# ignition4.net
KiCad netlist of a schematic drawn in EAGLE
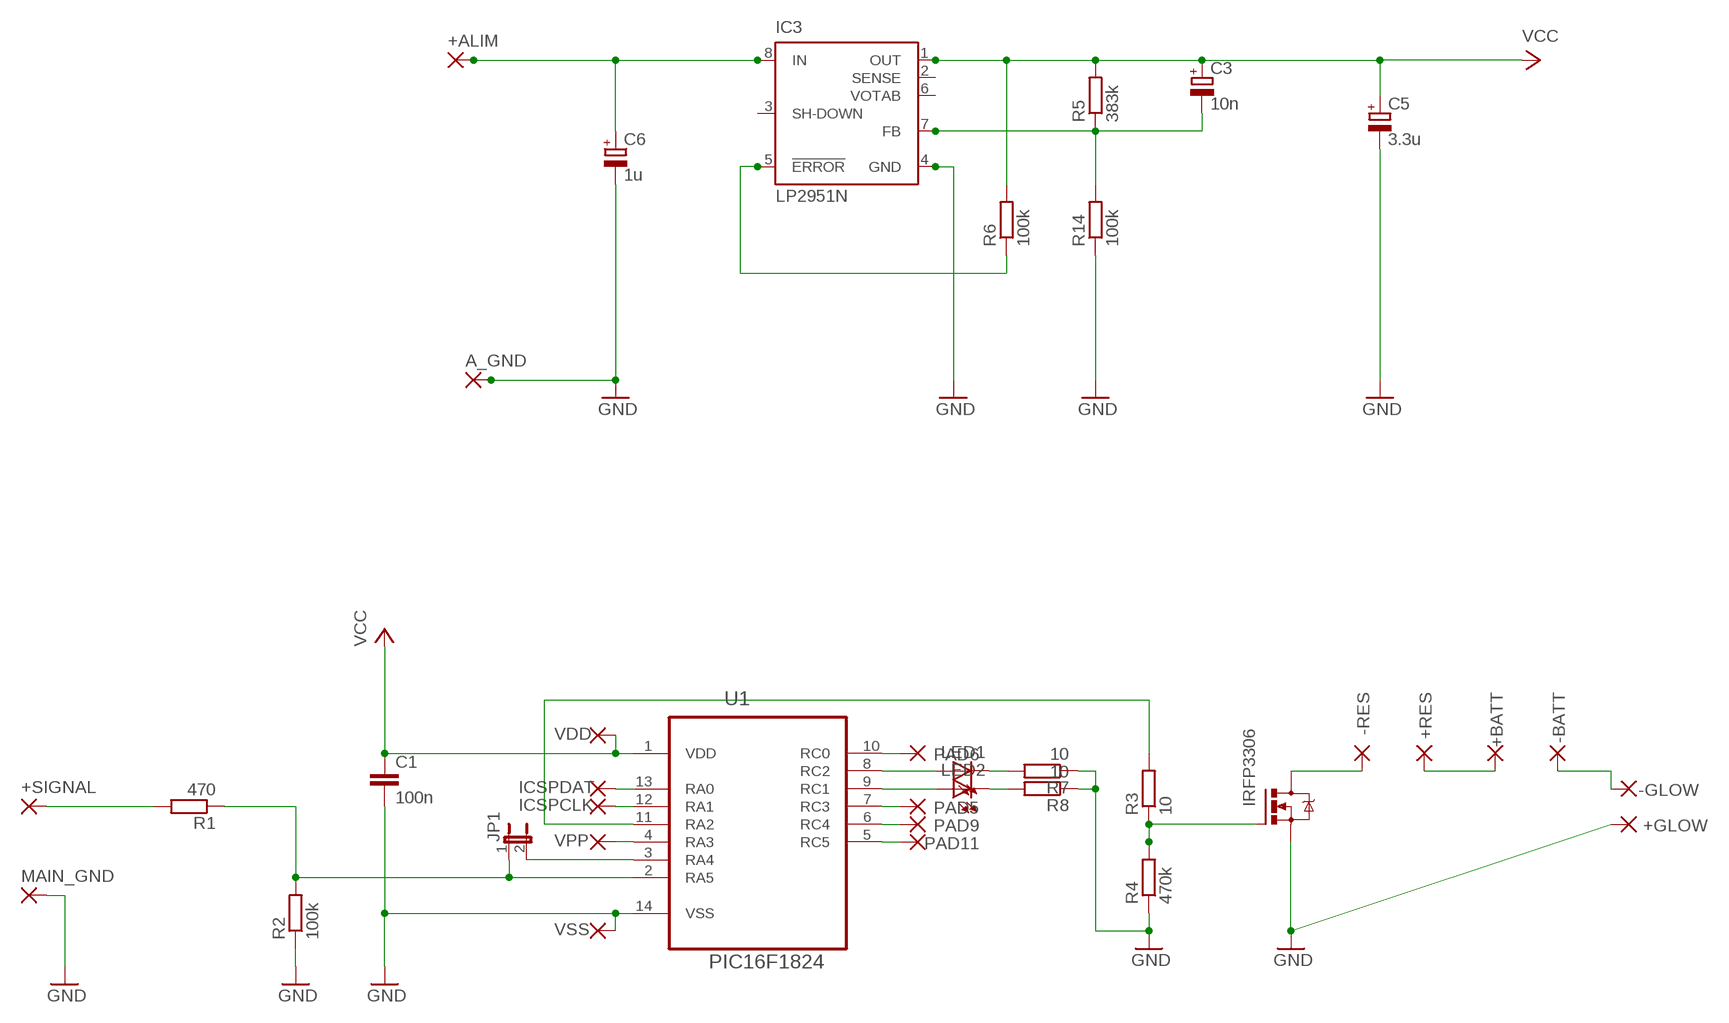
[diagram p0: schematic, sheet 1]

(export (version "E")
  (design (tool "Eeschema 10.0.6"))
  (components
    (comp (ref "+ALIM")
      (value "2,15/1,0")
      (footprint "eagle-import:2,15_1,0")
      (libsource (lib "eagle-import") (part "2,15/1,0"))
    )
    (comp (ref "+BATT")
      (value "WIREPAD3,17/1,3")
      (footprint "eagle-import:3,17_1,3")
      (libsource (lib "eagle-import") (part "WIREPAD3,17/1,3"))
    )
    (comp (ref "+GLOW")
      (value "WIREPAD3,17/1,3")
      (footprint "eagle-import:3,17_1,3")
      (libsource (lib "eagle-import") (part "WIREPAD3,17/1,3"))
    )
    (comp (ref "+RES")
      (value "WIREPAD3,17/1,3")
      (footprint "eagle-import:3,17_1,3")
      (libsource (lib "eagle-import") (part "WIREPAD3,17/1,3"))
    )
    (comp (ref "+SIGNAL")
      (value "2,15/1,0")
      (footprint "eagle-import:2,15_1,0")
      (libsource (lib "eagle-import") (part "2,15/1,0"))
    )
    (comp (ref "-BATT")
      (value "WIREPAD3,17/1,3")
      (footprint "eagle-import:3,17_1,3")
      (libsource (lib "eagle-import") (part "WIREPAD3,17/1,3"))
    )
    (comp (ref "-GLOW")
      (value "WIREPAD3,17/1,3")
      (footprint "eagle-import:3,17_1,3")
      (libsource (lib "eagle-import") (part "WIREPAD3,17/1,3"))
    )
    (comp (ref "-RES")
      (value "WIREPAD3,17/1,3")
      (footprint "eagle-import:3,17_1,3")
      (libsource (lib "eagle-import") (part "WIREPAD3,17/1,3"))
    )
    (comp (ref "A_GND")
      (value "2,15/1,0")
      (footprint "eagle-import:2,15_1,0")
      (libsource (lib "eagle-import") (part "2,15/1,0"))
    )
    (comp (ref "C1")
      (value "100n")
      (footprint "eagle-import:C050-035X075")
      (libsource (lib "eagle-import") (part "C-EU050-035X075"))
    )
    (comp (ref "C3")
      (value "10n")
      (footprint "eagle-import:E5-6")
      (libsource (lib "eagle-import") (part "CPOL-EUE5-6"))
    )
    (comp (ref "C5")
      (value "3.3u")
      (footprint "eagle-import:E2,5-5")
      (libsource (lib "eagle-import") (part "CPOL-EUE2.5-5"))
    )
    (comp (ref "C6")
      (value "1u")
      (footprint "eagle-import:E2,5-5")
      (libsource (lib "eagle-import") (part "CPOL-EUE2.5-5"))
    )
    (comp (ref "IC3")
      (value "LP2951N")
      (footprint "eagle-import:DIL08")
      (libsource (lib "eagle-import") (part "LP2951N"))
    )
    (comp (ref "ICSPCLK")
      (value "2,15/1,0")
      (footprint "eagle-import:2,15_1,0")
      (libsource (lib "eagle-import") (part "2,15/1,0"))
    )
    (comp (ref "ICSPDAT")
      (value "2,15/1,0")
      (footprint "eagle-import:2,15_1,0")
      (libsource (lib "eagle-import") (part "2,15/1,0"))
    )
    (comp (ref "JP1")
      (value "JP1E")
      (footprint "eagle-import:JP1")
      (libsource (lib "eagle-import") (part "JP1E"))
    )
    (comp (ref "LED1")
      (value "LED3MM")
      (footprint "eagle-import:LED3MM")
      (libsource (lib "eagle-import") (part "LED3MM"))
    )
    (comp (ref "LED2")
      (value "LED3MM")
      (footprint "eagle-import:LED3MM")
      (libsource (lib "eagle-import") (part "LED3MM"))
    )
    (comp (ref "MAIN_GND")
      (value "2,15/1,0")
      (footprint "eagle-import:2,15_1,0")
      (libsource (lib "eagle-import") (part "2,15/1,0"))
    )
    (comp (ref "PAD5")
      (value "2,15/1,0")
      (footprint "eagle-import:2,15_1,0")
      (libsource (lib "eagle-import") (part "2,15/1,0"))
    )
    (comp (ref "PAD6")
      (value "2,15/1,0")
      (footprint "eagle-import:2,15_1,0")
      (libsource (lib "eagle-import") (part "2,15/1,0"))
    )
    (comp (ref "PAD9")
      (value "2,15/1,0")
      (footprint "eagle-import:2,15_1,0")
      (libsource (lib "eagle-import") (part "2,15/1,0"))
    )
    (comp (ref "PAD11")
      (value "2,15/1,0")
      (footprint "eagle-import:2,15_1,0")
      (libsource (lib "eagle-import") (part "2,15/1,0"))
    )
    (comp (ref "Q2")
      (value "IRFP3306")
      (footprint "eagle-import:TO247BV")
      (libsource (lib "eagle-import") (part "IRFPC40"))
    )
    (comp (ref "R1")
      (value "470")
      (footprint "eagle-import:0207_7")
      (libsource (lib "eagle-import") (part "R-EU_0207/7"))
    )
    (comp (ref "R2")
      (value "100k")
      (footprint "eagle-import:0207_7")
      (libsource (lib "eagle-import") (part "R-EU_0207/7"))
    )
    (comp (ref "R3")
      (value "10")
      (footprint "eagle-import:0207_7")
      (libsource (lib "eagle-import") (part "R-EU_0207/7"))
    )
    (comp (ref "R4")
      (value "470k")
      (footprint "eagle-import:0207_7")
      (libsource (lib "eagle-import") (part "R-EU_0207/7"))
    )
    (comp (ref "R5")
      (value "383k")
      (footprint "eagle-import:0207_7")
      (libsource (lib "eagle-import") (part "R-EU_0207/7"))
    )
    (comp (ref "R6")
      (value "100k")
      (footprint "eagle-import:0207_7")
      (libsource (lib "eagle-import") (part "R-EU_0207/7"))
    )
    (comp (ref "R7")
      (value "10")
      (footprint "eagle-import:0207_7")
      (libsource (lib "eagle-import") (part "R-EU_0207/7"))
    )
    (comp (ref "R8")
      (value "10")
      (footprint "eagle-import:0207_7")
      (libsource (lib "eagle-import") (part "R-EU_0207/7"))
    )
    (comp (ref "R14")
      (value "100k")
      (footprint "eagle-import:0207_7")
      (libsource (lib "eagle-import") (part "R-EU_0207/7"))
    )
    (comp (ref "U1")
      (value "PIC16F1824")
      (footprint "eagle-import:DIP254P762X533-14")
      (fields (field (name "MPN") "PIC16F1824-I/P"))
      (libsource (lib "eagle-import") (part "PIC16F1824-I/P"))
    )
    (comp (ref "VDD")
      (value "WIREPAD2,15/1,0")
      (footprint "eagle-import:2,15_1,0")
      (libsource (lib "eagle-import") (part "WIREPAD2,15/1,0"))
    )
    (comp (ref "VPP")
      (value "2,15/1,0")
      (footprint "eagle-import:2,15_1,0")
      (libsource (lib "eagle-import") (part "2,15/1,0"))
    )
    (comp (ref "VSS")
      (value "WIREPAD2,15/1,0")
      (footprint "eagle-import:2,15_1,0")
      (libsource (lib "eagle-import") (part "WIREPAD2,15/1,0"))
    )
  )
  (nets
    (net (code "1") (name "GND") (class "Default")
      (node (ref "+GLOW") (pin "1") (pinfunction "P_1") (pintype "passive"))
      (node (ref "A_GND") (pin "1") (pinfunction "P_1") (pintype "passive"))
      (node (ref "C1") (pin "2") (pinfunction "2_2") (pintype "passive"))
      (node (ref "C5") (pin "-") (pinfunction "-_-") (pintype "passive"))
      (node (ref "C6") (pin "-") (pinfunction "-_-") (pintype "passive"))
      (node (ref "IC3") (pin "4") (pinfunction "GND_4") (pintype "power_in"))
      (node (ref "MAIN_GND") (pin "1") (pinfunction "P_1") (pintype "passive"))
      (node (ref "Q2") (pin "S") (pinfunction "S_S") (pintype "passive"))
      (node (ref "R14") (pin "1") (pinfunction "1_1") (pintype "passive"))
      (node (ref "R2") (pin "1") (pinfunction "1_1") (pintype "passive"))
      (node (ref "R4") (pin "1") (pinfunction "1_1") (pintype "passive"))
      (node (ref "R7") (pin "1") (pinfunction "1_1") (pintype "passive"))
      (node (ref "R8") (pin "1") (pinfunction "1_1") (pintype "passive"))
      (node (ref "U1") (pin "14") (pinfunction "VSS_14") (pintype "power_in"))
      (node (ref "VSS") (pin "1") (pinfunction "P_1") (pintype "passive"))
    )
    (net (code "2") (name "Net-(+ALIM-P)") (class "Default")
      (node (ref "+ALIM") (pin "1") (pinfunction "P_1") (pintype "passive"))
      (node (ref "C6") (pin "+") (pinfunction "+_+") (pintype "passive"))
      (node (ref "IC3") (pin "8") (pinfunction "IN_8") (pintype "input"))
    )
    (net (code "3") (name "Net-(+BATT-P)") (class "Default")
      (node (ref "+BATT") (pin "1") (pinfunction "P_1") (pintype "passive"))
      (node (ref "+RES") (pin "1") (pinfunction "P_1") (pintype "passive"))
    )
    (net (code "4") (name "Net-(+SIGNAL-P)") (class "Default")
      (node (ref "+SIGNAL") (pin "1") (pinfunction "P_1") (pintype "passive"))
      (node (ref "R1") (pin "2") (pinfunction "2_2") (pintype "passive"))
    )
    (net (code "5") (name "Net-(-BATT-P)") (class "Default")
      (node (ref "-BATT") (pin "1") (pinfunction "P_1") (pintype "passive"))
      (node (ref "-GLOW") (pin "1") (pinfunction "P_1") (pintype "passive"))
    )
    (net (code "6") (name "Net-(-RES-P)") (class "Default")
      (node (ref "-RES") (pin "1") (pinfunction "P_1") (pintype "passive"))
      (node (ref "Q2") (pin "D") (pinfunction "D_D") (pintype "passive"))
    )
    (net (code "7") (name "Net-(IC3-FB)") (class "Default")
      (node (ref "C3") (pin "-") (pinfunction "-_-") (pintype "passive"))
      (node (ref "IC3") (pin "7") (pinfunction "FB_7") (pintype "input"))
      (node (ref "R14") (pin "2") (pinfunction "2_2") (pintype "passive"))
      (node (ref "R5") (pin "1") (pinfunction "1_1") (pintype "passive"))
    )
    (net (code "8") (name "Net-(IC3-~{ERROR})") (class "Default")
      (node (ref "IC3") (pin "5") (pinfunction "~{ERROR}_5") (pintype "output"))
      (node (ref "R6") (pin "1") (pinfunction "1_1") (pintype "passive"))
    )
    (net (code "9") (name "Net-(ICSPCLK-P)") (class "Default")
      (node (ref "ICSPCLK") (pin "1") (pinfunction "P_1") (pintype "passive"))
      (node (ref "U1") (pin "12") (pinfunction "RA1_12") (pintype "bidirectional"))
    )
    (net (code "10") (name "Net-(ICSPDAT-P)") (class "Default")
      (node (ref "ICSPDAT") (pin "1") (pinfunction "P_1") (pintype "passive"))
      (node (ref "U1") (pin "13") (pinfunction "RA0_13") (pintype "bidirectional"))
    )
    (net (code "11") (name "Net-(LED1-C)") (class "Default")
      (node (ref "LED1") (pin "K") (pinfunction "C_K") (pintype "passive"))
      (node (ref "R7") (pin "2") (pinfunction "2_2") (pintype "passive"))
    )
    (net (code "12") (name "Net-(LED2-C)") (class "Default")
      (node (ref "LED2") (pin "K") (pinfunction "C_K") (pintype "passive"))
      (node (ref "R8") (pin "2") (pinfunction "2_2") (pintype "passive"))
    )
    (net (code "13") (name "Net-(PAD5-P)") (class "Default")
      (node (ref "PAD5") (pin "1") (pinfunction "P_1") (pintype "passive"))
      (node (ref "U1") (pin "7") (pinfunction "RC3_7") (pintype "bidirectional"))
    )
    (net (code "14") (name "Net-(PAD6-P)") (class "Default")
      (node (ref "PAD6") (pin "1") (pinfunction "P_1") (pintype "passive"))
      (node (ref "U1") (pin "10") (pinfunction "RC0_10") (pintype "bidirectional"))
    )
    (net (code "15") (name "Net-(PAD9-P)") (class "Default")
      (node (ref "PAD9") (pin "1") (pinfunction "P_1") (pintype "passive"))
      (node (ref "U1") (pin "6") (pinfunction "RC4_6") (pintype "bidirectional"))
    )
    (net (code "16") (name "Net-(PAD11-P)") (class "Default")
      (node (ref "PAD11") (pin "1") (pinfunction "P_1") (pintype "passive"))
      (node (ref "U1") (pin "5") (pinfunction "RC5_5") (pintype "bidirectional"))
    )
    (net (code "17") (name "Net-(Q2-PadG)") (class "Default")
      (node (ref "Q2") (pin "G") (pinfunction "G_G") (pintype "passive"))
      (node (ref "R3") (pin "1") (pinfunction "1_1") (pintype "passive"))
      (node (ref "R4") (pin "2") (pinfunction "2_2") (pintype "passive"))
    )
    (net (code "18") (name "Net-(U1-RA2)") (class "Default")
      (node (ref "R3") (pin "2") (pinfunction "2_2") (pintype "passive"))
      (node (ref "U1") (pin "11") (pinfunction "RA2_11") (pintype "bidirectional"))
    )
    (net (code "19") (name "Net-(U1-RA3)") (class "Default")
      (node (ref "U1") (pin "4") (pinfunction "RA3_4") (pintype "input"))
      (node (ref "VPP") (pin "1") (pinfunction "P_1") (pintype "passive"))
    )
    (net (code "20") (name "Net-(U1-RA4)") (class "Default")
      (node (ref "JP1") (pin "2") (pinfunction "2_2") (pintype "passive"))
      (node (ref "U1") (pin "3") (pinfunction "RA4_3") (pintype "bidirectional"))
    )
    (net (code "21") (name "Net-(U1-RA5)") (class "Default")
      (node (ref "JP1") (pin "1") (pinfunction "1_1") (pintype "passive"))
      (node (ref "R1") (pin "1") (pinfunction "1_1") (pintype "passive"))
      (node (ref "R2") (pin "2") (pinfunction "2_2") (pintype "passive"))
      (node (ref "U1") (pin "2") (pinfunction "RA5_2") (pintype "bidirectional"))
    )
    (net (code "22") (name "Net-(U1-RC1)") (class "Default")
      (node (ref "LED2") (pin "A") (pinfunction "A_A") (pintype "passive"))
      (node (ref "U1") (pin "9") (pinfunction "RC1_9") (pintype "bidirectional"))
    )
    (net (code "23") (name "Net-(U1-RC2)") (class "Default")
      (node (ref "LED1") (pin "A") (pinfunction "A_A") (pintype "passive"))
      (node (ref "U1") (pin "8") (pinfunction "RC2_8") (pintype "bidirectional"))
    )
    (net (code "24") (name "VCC") (class "Default")
      (node (ref "C1") (pin "1") (pinfunction "1_1") (pintype "passive"))
      (node (ref "C3") (pin "+") (pinfunction "+_+") (pintype "passive"))
      (node (ref "C5") (pin "+") (pinfunction "+_+") (pintype "passive"))
      (node (ref "IC3") (pin "1") (pinfunction "OUT_1") (pintype "input"))
      (node (ref "R5") (pin "2") (pinfunction "2_2") (pintype "passive"))
      (node (ref "R6") (pin "2") (pinfunction "2_2") (pintype "passive"))
      (node (ref "U1") (pin "1") (pinfunction "VDD_1") (pintype "power_in"))
      (node (ref "VDD") (pin "1") (pinfunction "P_1") (pintype "passive"))
    )
    (net (code "25") (name "unconnected-(IC3-SENSE-Pad2)") (class "Default")
      (node (ref "IC3") (pin "2") (pinfunction "SENSE_2") (pintype "input"))
    )
    (net (code "26") (name "unconnected-(IC3-SH-DOWN-Pad3)") (class "Default")
      (node (ref "IC3") (pin "3") (pinfunction "SH-DOWN_3") (pintype "input"))
    )
    (net (code "27") (name "unconnected-(IC3-VOTAB-Pad6)") (class "Default")
      (node (ref "IC3") (pin "6") (pinfunction "VOTAB_6") (pintype "passive"))
    )
  )
)
